# breakout.net
KiCad netlist of a schematic drawn in Altium Designer
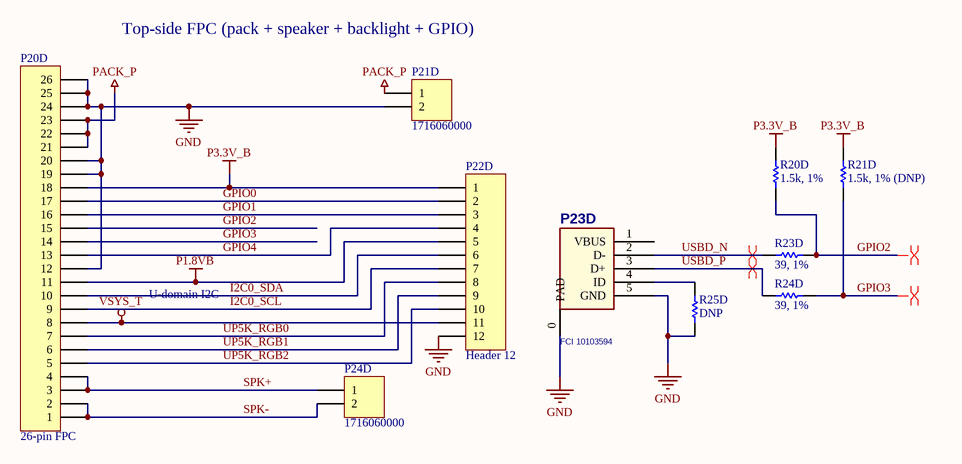
[diagram p0: breakout.SchDoc]

(export (version "E")
  (design (tool "Eeschema 10.0.6"))
  (components
    (comp (ref "P20D")
      (value "26-pin FPC")
      (footprint "HRS_FH34SRJ-26S-0.5SH(50)")
      (description "26 Pin FPC header")
      (fields (field (name "MPN") "FH34SRJ-26S-0.5SH(99)"))
      (libsource (lib "commonsch-new") (part "FPC-26"))
    )
    (comp (ref "P21D")
      (value "1716060000")
      (footprint "weidmuller_1716060000")
      (description "Header, 2-Pin")
      (fields (field (name "PUBLISHER") "Altium Limited"))
      (libsource (lib "Miscellaneous Connectors") (part "Header 2"))
    )
    (comp (ref "P22D")
      (value "Header 12")
      (footprint "HDR1X12")
      (description "Header, 12-Pin")
      (fields (field (name "PUBLISHER") "Altium Limited"))
      (libsource (lib "Miscellaneous Connectors") (part "Header 12"))
    )
    (comp (ref "P23D")
      (value "FCI 10103594")
      (footprint "USB_MICRO_B_SMT")
      (description "Micro USB B type connector")
      (fields (field (name "MPN") "10103594-0001LF"))
      (libsource (lib "*") (part "USB_MINI-AB_1"))
    )
    (comp (ref "P24D")
      (value "1716060000")
      (footprint "weidmuller_1716060000")
      (description "Header, 2-Pin")
      (fields (field (name "PUBLISHER") "Altium Limited"))
      (libsource (lib "Miscellaneous Connectors") (part "Header 2"))
    )
    (comp (ref "R20D")
      (value "1.5k, 1%")
      (footprint "B_RES0402")
      (description "Resistor")
      (fields (field (name "MPN") "RS02U152FT"))
      (libsource (lib "Miscellaneous Devices") (part "Res1"))
    )
    (comp (ref "R21D")
      (value "1.5k, 1% (DNP)")
      (footprint "B_RES0402")
      (description "Resistor")
      (fields (field (name "MPN") "DNP"))
      (libsource (lib "Miscellaneous Devices") (part "Res1"))
    )
    (comp (ref "R23D")
      (value "39, 1%")
      (footprint "B_RES0402")
      (description "Resistor")
      (fields (field (name "MPN") "ANY"))
      (libsource (lib "Miscellaneous Devices") (part "Res1"))
    )
    (comp (ref "R24D")
      (value "39, 1%")
      (footprint "B_RES0402")
      (description "Resistor")
      (fields (field (name "MPN") "ANY"))
      (libsource (lib "Miscellaneous Devices") (part "Res1"))
    )
    (comp (ref "R25D")
      (value "DNP")
      (footprint "B_RES0402")
      (description "Resistor")
      (fields (field (name "MPN") "ANY"))
      (libsource (lib "Miscellaneous Devices") (part "Res1"))
    )
  )
  (nets
    (net (code "1") (name "/GPIO0") (class "Default")
      (node (ref "P20D") (pin "17") (pinfunction "17_17") (pintype "passive"))
      (node (ref "P22D") (pin "2") (pinfunction "2_2") (pintype "passive"))
    )
    (net (code "2") (name "/GPIO1") (class "Default")
      (node (ref "P20D") (pin "16") (pinfunction "16_16") (pintype "passive"))
      (node (ref "P22D") (pin "3") (pinfunction "3_3") (pintype "passive"))
    )
    (net (code "3") (name "/GPIO2") (class "Default")
      (node (ref "P20D") (pin "15") (pinfunction "15_15") (pintype "passive"))
      (node (ref "R20D") (pin "2") (pinfunction "2_2") (pintype "passive"))
      (node (ref "R23D") (pin "1") (pinfunction "1_1") (pintype "passive"))
    )
    (net (code "4") (name "/GPIO3") (class "Default")
      (node (ref "P20D") (pin "14") (pinfunction "14_14") (pintype "passive"))
      (node (ref "R21D") (pin "2") (pinfunction "2_2") (pintype "passive"))
      (node (ref "R24D") (pin "1") (pinfunction "1_1") (pintype "passive"))
    )
    (net (code "5") (name "/GPIO4") (class "Default")
      (node (ref "P20D") (pin "13") (pinfunction "13_13") (pintype "passive"))
      (node (ref "P22D") (pin "4") (pinfunction "4_4") (pintype "passive"))
    )
    (net (code "6") (name "/I2C0_SCL") (class "Default")
      (node (ref "P20D") (pin "9") (pinfunction "9_9") (pintype "passive"))
      (node (ref "P22D") (pin "7") (pinfunction "7_7") (pintype "passive"))
    )
    (net (code "7") (name "/I2C0_SDA") (class "Default")
      (node (ref "P20D") (pin "10") (pinfunction "10_10") (pintype "passive"))
      (node (ref "P22D") (pin "6") (pinfunction "6_6") (pintype "passive"))
    )
    (net (code "8") (name "/SPK+") (class "Default")
      (node (ref "P20D") (pin "3") (pinfunction "3_3") (pintype "passive"))
      (node (ref "P20D") (pin "4") (pinfunction "4_4") (pintype "passive"))
      (node (ref "P24D") (pin "1") (pinfunction "1_1") (pintype "passive"))
    )
    (net (code "9") (name "/SPK-") (class "Default")
      (node (ref "P20D") (pin "1") (pinfunction "1_1") (pintype "passive"))
      (node (ref "P20D") (pin "2") (pinfunction "2_2") (pintype "passive"))
      (node (ref "P24D") (pin "2") (pinfunction "2_2") (pintype "passive"))
    )
    (net (code "10") (name "/UP5K_RGB0") (class "Default")
      (node (ref "P20D") (pin "7") (pinfunction "7_7") (pintype "passive"))
      (node (ref "P22D") (pin "8") (pinfunction "8_8") (pintype "passive"))
    )
    (net (code "11") (name "/UP5K_RGB1") (class "Default")
      (node (ref "P20D") (pin "6") (pinfunction "6_6") (pintype "passive"))
      (node (ref "P22D") (pin "9") (pinfunction "9_9") (pintype "passive"))
    )
    (net (code "12") (name "/UP5K_RGB2") (class "Default")
      (node (ref "P20D") (pin "5") (pinfunction "5_5") (pintype "passive"))
      (node (ref "P22D") (pin "10") (pinfunction "10_10") (pintype "passive"))
    )
    (net (code "13") (name "/USBD_N") (class "Default")
      (node (ref "P23D") (pin "2") (pinfunction "D-_2") (pintype "passive"))
      (node (ref "R23D") (pin "2") (pinfunction "2_2") (pintype "passive"))
    )
    (net (code "14") (name "/USBD_P") (class "Default")
      (node (ref "P23D") (pin "3") (pinfunction "D+_3") (pintype "passive"))
      (node (ref "R24D") (pin "2") (pinfunction "2_2") (pintype "passive"))
    )
    (net (code "15") (name "GND") (class "Default")
      (node (ref "P20D") (pin "12") (pinfunction "12_12") (pintype "passive"))
      (node (ref "P20D") (pin "19") (pinfunction "19_19") (pintype "passive"))
      (node (ref "P20D") (pin "20") (pinfunction "20_20") (pintype "passive"))
      (node (ref "P20D") (pin "24") (pinfunction "24_24") (pintype "passive"))
      (node (ref "P20D") (pin "25") (pinfunction "25_25") (pintype "passive"))
      (node (ref "P20D") (pin "26") (pinfunction "26_26") (pintype "passive"))
      (node (ref "P21D") (pin "2") (pinfunction "2_2") (pintype "passive"))
      (node (ref "P22D") (pin "12") (pinfunction "12_12") (pintype "passive"))
      (node (ref "P23D") (pin "0") (pinfunction "PAD_0") (pintype "passive"))
      (node (ref "P23D") (pin "5") (pinfunction "GND_5") (pintype "passive"))
      (node (ref "R25D") (pin "2") (pinfunction "2_2") (pintype "passive"))
    )
    (net (code "16") (name "Net-(P23D-ID)") (class "Default")
      (node (ref "P23D") (pin "4") (pinfunction "ID_4") (pintype "passive"))
      (node (ref "R25D") (pin "1") (pinfunction "1_1") (pintype "passive"))
    )
    (net (code "17") (name "P1.8VB") (class "Default")
      (node (ref "P20D") (pin "11") (pinfunction "11_11") (pintype "passive"))
      (node (ref "P22D") (pin "5") (pinfunction "5_5") (pintype "passive"))
    )
    (net (code "18") (name "P3.3V_B") (class "Default")
      (node (ref "P20D") (pin "18") (pinfunction "18_18") (pintype "passive"))
      (node (ref "P22D") (pin "1") (pinfunction "1_1") (pintype "passive"))
      (node (ref "R20D") (pin "1") (pinfunction "1_1") (pintype "passive"))
      (node (ref "R21D") (pin "1") (pinfunction "1_1") (pintype "passive"))
    )
    (net (code "19") (name "PACK_P") (class "Default")
      (node (ref "P20D") (pin "21") (pinfunction "21_21") (pintype "passive"))
      (node (ref "P20D") (pin "22") (pinfunction "22_22") (pintype "passive"))
      (node (ref "P20D") (pin "23") (pinfunction "23_23") (pintype "passive"))
      (node (ref "P21D") (pin "1") (pinfunction "1_1") (pintype "passive"))
    )
    (net (code "20") (name "VSYS_T") (class "Default")
      (node (ref "P20D") (pin "8") (pinfunction "8_8") (pintype "passive"))
      (node (ref "P22D") (pin "11") (pinfunction "11_11") (pintype "passive"))
    )
    (net (code "21") (name "unconnected-(P23D-VBUS-Pad1)") (class "Default")
      (node (ref "P23D") (pin "1") (pinfunction "VBUS_1") (pintype "passive"))
    )
  )
)
